# String_Thing_1_0.net
KiCad netlist of a schematic drawn in EAGLE
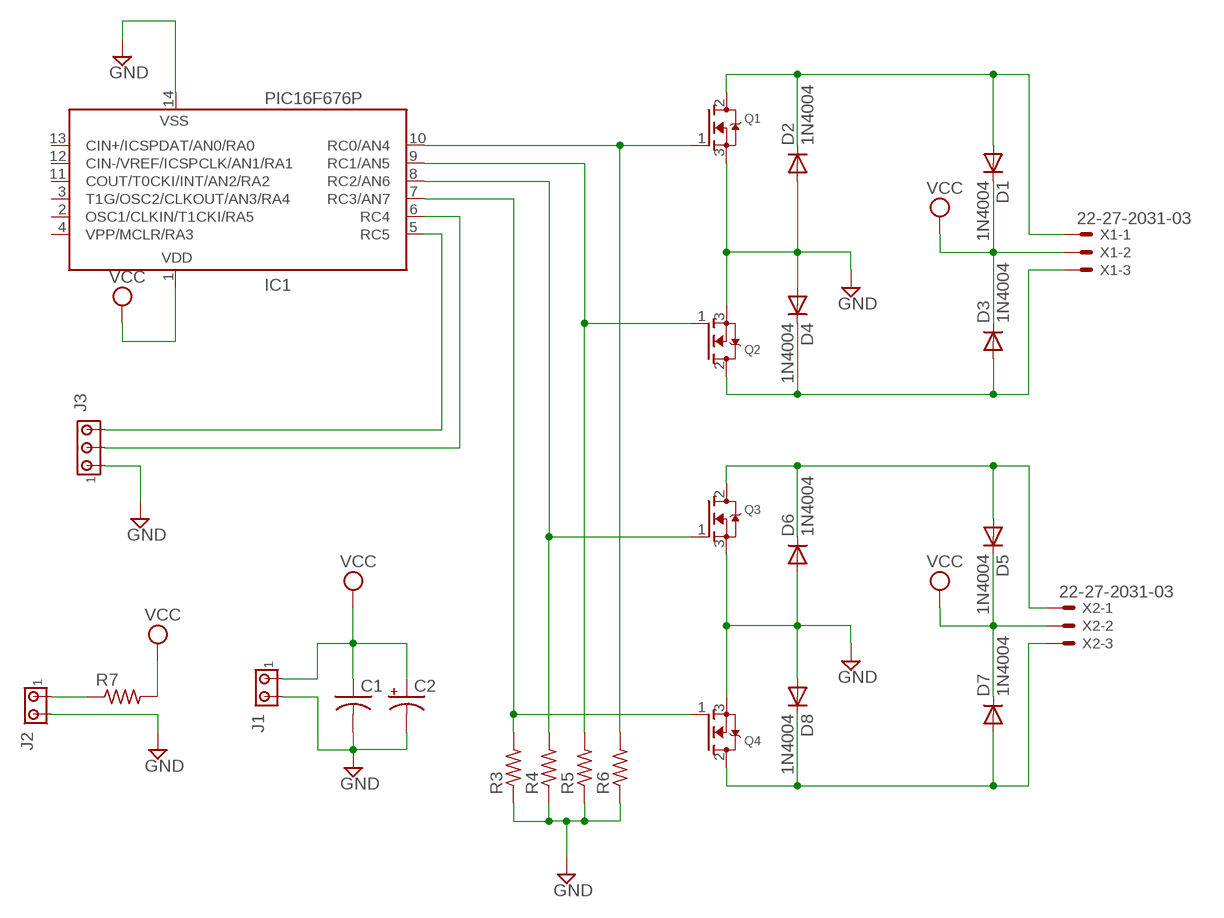
[diagram p0: schematic, sheet 1]

(export (version "E")
  (design (tool "Eeschema 10.0.6"))
  (components
    (comp (ref "C1")
      (value "C-US025-025X050")
      (footprint "eagle-import:C025-025X050")
      (libsource (lib "eagle-import") (part "C-US025-025X050"))
    )
    (comp (ref "C2")
      (value "CPOL-USE2.5-5")
      (footprint "eagle-import:E2,5-5")
      (libsource (lib "eagle-import") (part "CPOL-USE2.5-5"))
    )
    (comp (ref "D1")
      (value "1N4004")
      (footprint "eagle-import:DO41-10")
      (libsource (lib "eagle-import") (part "1N4004"))
    )
    (comp (ref "D2")
      (value "1N4004")
      (footprint "eagle-import:DO41-10")
      (libsource (lib "eagle-import") (part "1N4004"))
    )
    (comp (ref "D3")
      (value "1N4004")
      (footprint "eagle-import:DO41-10")
      (libsource (lib "eagle-import") (part "1N4004"))
    )
    (comp (ref "D4")
      (value "1N4004")
      (footprint "eagle-import:DO41-10")
      (libsource (lib "eagle-import") (part "1N4004"))
    )
    (comp (ref "D5")
      (value "1N4004")
      (footprint "eagle-import:DO41-10")
      (libsource (lib "eagle-import") (part "1N4004"))
    )
    (comp (ref "D6")
      (value "1N4004")
      (footprint "eagle-import:DO41-10")
      (libsource (lib "eagle-import") (part "1N4004"))
    )
    (comp (ref "D7")
      (value "1N4004")
      (footprint "eagle-import:DO41-10")
      (libsource (lib "eagle-import") (part "1N4004"))
    )
    (comp (ref "D8")
      (value "1N4004")
      (footprint "eagle-import:DO41-10")
      (libsource (lib "eagle-import") (part "1N4004"))
    )
    (comp (ref "IC1")
      (value "PIC16F676P")
      (footprint "eagle-import:DIL14")
      (fields (field (name "MF") "MICROCHIP") (field (name "MPN") "PIC16F676-I/P"))
      (libsource (lib "eagle-import") (part "PIC16F676P"))
    )
    (comp (ref "J1")
      (value "MTA02-100")
      (footprint "eagle-import:10X02MTA")
      (libsource (lib "eagle-import") (part "MTA02-100"))
    )
    (comp (ref "J2")
      (value "MTA02-100")
      (footprint "eagle-import:10X02MTA")
      (libsource (lib "eagle-import") (part "MTA02-100"))
    )
    (comp (ref "J3")
      (value "MTA03-100")
      (footprint "eagle-import:10X03MTA")
      (libsource (lib "eagle-import") (part "MTA03-100"))
    )
    (comp (ref "Q1")
      (value "MOSFET-NGDS_TO220V")
      (footprint "eagle-import:TO220V")
      (libsource (lib "eagle-import") (part "MOSFET-NGDS_TO220V"))
    )
    (comp (ref "Q2")
      (value "MOSFET-NGDS_TO220V")
      (footprint "eagle-import:TO220V")
      (libsource (lib "eagle-import") (part "MOSFET-NGDS_TO220V"))
    )
    (comp (ref "Q3")
      (value "MOSFET-NGDS_TO220V")
      (footprint "eagle-import:TO220V")
      (libsource (lib "eagle-import") (part "MOSFET-NGDS_TO220V"))
    )
    (comp (ref "Q4")
      (value "MOSFET-NGDS_TO220V")
      (footprint "eagle-import:TO220V")
      (libsource (lib "eagle-import") (part "MOSFET-NGDS_TO220V"))
    )
    (comp (ref "R3")
      (value "R-US_0207/10")
      (footprint "eagle-import:0207_10")
      (libsource (lib "eagle-import") (part "R-US_0207/10"))
    )
    (comp (ref "R4")
      (value "R-US_0207/10")
      (footprint "eagle-import:0207_10")
      (libsource (lib "eagle-import") (part "R-US_0207/10"))
    )
    (comp (ref "R5")
      (value "R-US_0207/10")
      (footprint "eagle-import:0207_10")
      (libsource (lib "eagle-import") (part "R-US_0207/10"))
    )
    (comp (ref "R6")
      (value "R-US_0207/10")
      (footprint "eagle-import:0207_10")
      (libsource (lib "eagle-import") (part "R-US_0207/10"))
    )
    (comp (ref "R7")
      (value "R-US_0207/10")
      (footprint "eagle-import:0207_10")
      (libsource (lib "eagle-import") (part "R-US_0207/10"))
    )
    (comp (ref "X1")
      (value "22-27-2031-03")
      (footprint "eagle-import:6410-03")
      (libsource (lib "eagle-import") (part "22-?-0327-2031"))
    )
    (comp (ref "X2")
      (value "22-27-2031-03")
      (footprint "eagle-import:6410-03")
      (libsource (lib "eagle-import") (part "22-?-0327-2031"))
    )
  )
  (nets
    (net (code "1") (name "GND") (class "Default")
      (node (ref "C1") (pin "2") (pinfunction "2_2") (pintype "passive"))
      (node (ref "C2") (pin "-") (pinfunction "-_-") (pintype "passive"))
      (node (ref "D2") (pin "A") (pinfunction "A_A") (pintype "passive"))
      (node (ref "D4") (pin "A") (pinfunction "A_A") (pintype "passive"))
      (node (ref "D6") (pin "A") (pinfunction "A_A") (pintype "passive"))
      (node (ref "D8") (pin "A") (pinfunction "A_A") (pintype "passive"))
      (node (ref "IC1") (pin "14") (pinfunction "VSS_14") (pintype "power_in"))
      (node (ref "J1") (pin "2") (pinfunction "2_2") (pintype "passive"))
      (node (ref "J2") (pin "2") (pinfunction "2_2") (pintype "passive"))
      (node (ref "J3") (pin "1") (pinfunction "1_1") (pintype "passive"))
      (node (ref "Q1") (pin "3") (pinfunction "S_3") (pintype "bidirectional"))
      (node (ref "Q2") (pin "3") (pinfunction "S_3") (pintype "bidirectional"))
      (node (ref "Q3") (pin "3") (pinfunction "S_3") (pintype "bidirectional"))
      (node (ref "Q4") (pin "3") (pinfunction "S_3") (pintype "bidirectional"))
      (node (ref "R3") (pin "1") (pinfunction "1_1") (pintype "passive"))
      (node (ref "R4") (pin "1") (pinfunction "1_1") (pintype "passive"))
      (node (ref "R5") (pin "1") (pinfunction "1_1") (pintype "passive"))
      (node (ref "R6") (pin "1") (pinfunction "1_1") (pintype "passive"))
    )
    (net (code "2") (name "Net-(IC1-RC0{slash}AN4)") (class "Default")
      (node (ref "IC1") (pin "10") (pinfunction "RC0/AN4_10") (pintype "bidirectional"))
      (node (ref "Q1") (pin "1") (pinfunction "G_1") (pintype "bidirectional"))
      (node (ref "R6") (pin "2") (pinfunction "2_2") (pintype "passive"))
    )
    (net (code "3") (name "Net-(IC1-RC1{slash}AN5)") (class "Default")
      (node (ref "IC1") (pin "9") (pinfunction "RC1/AN5_9") (pintype "bidirectional"))
      (node (ref "Q2") (pin "1") (pinfunction "G_1") (pintype "bidirectional"))
      (node (ref "R5") (pin "2") (pinfunction "2_2") (pintype "passive"))
    )
    (net (code "4") (name "Net-(IC1-RC2{slash}AN6)") (class "Default")
      (node (ref "IC1") (pin "8") (pinfunction "RC2/AN6_8") (pintype "bidirectional"))
      (node (ref "Q3") (pin "1") (pinfunction "G_1") (pintype "bidirectional"))
      (node (ref "R4") (pin "2") (pinfunction "2_2") (pintype "passive"))
    )
    (net (code "5") (name "Net-(IC1-RC3{slash}AN7)") (class "Default")
      (node (ref "IC1") (pin "7") (pinfunction "RC3/AN7_7") (pintype "bidirectional"))
      (node (ref "Q4") (pin "1") (pinfunction "G_1") (pintype "bidirectional"))
      (node (ref "R3") (pin "2") (pinfunction "2_2") (pintype "passive"))
    )
    (net (code "6") (name "Net-(IC1-RC4)") (class "Default")
      (node (ref "IC1") (pin "6") (pinfunction "RC4_6") (pintype "bidirectional"))
      (node (ref "J3") (pin "2") (pinfunction "2_2") (pintype "passive"))
    )
    (net (code "7") (name "Net-(IC1-RC5)") (class "Default")
      (node (ref "IC1") (pin "5") (pinfunction "RC5_5") (pintype "bidirectional"))
      (node (ref "J3") (pin "3") (pinfunction "3_3") (pintype "passive"))
    )
    (net (code "8") (name "Net-(J2-Pad1)") (class "Default")
      (node (ref "J2") (pin "1") (pinfunction "1_1") (pintype "passive"))
      (node (ref "R7") (pin "1") (pinfunction "1_1") (pintype "passive"))
    )
    (net (code "9") (name "Net-(Q1-D)") (class "Default")
      (node (ref "D1") (pin "A") (pinfunction "A_A") (pintype "passive"))
      (node (ref "D2") (pin "C") (pinfunction "C_C") (pintype "passive"))
      (node (ref "Q1") (pin "2") (pinfunction "D_2") (pintype "bidirectional"))
      (node (ref "X1") (pin "1") (pinfunction "S_1") (pintype "passive"))
    )
    (net (code "10") (name "Net-(Q2-D)") (class "Default")
      (node (ref "D3") (pin "A") (pinfunction "A_A") (pintype "passive"))
      (node (ref "D4") (pin "C") (pinfunction "C_C") (pintype "passive"))
      (node (ref "Q2") (pin "2") (pinfunction "D_2") (pintype "bidirectional"))
      (node (ref "X1") (pin "3") (pinfunction "S_3") (pintype "passive"))
    )
    (net (code "11") (name "Net-(Q3-D)") (class "Default")
      (node (ref "D5") (pin "A") (pinfunction "A_A") (pintype "passive"))
      (node (ref "D6") (pin "C") (pinfunction "C_C") (pintype "passive"))
      (node (ref "Q3") (pin "2") (pinfunction "D_2") (pintype "bidirectional"))
      (node (ref "X2") (pin "1") (pinfunction "S_1") (pintype "passive"))
    )
    (net (code "12") (name "Net-(Q4-D)") (class "Default")
      (node (ref "D7") (pin "A") (pinfunction "A_A") (pintype "passive"))
      (node (ref "D8") (pin "C") (pinfunction "C_C") (pintype "passive"))
      (node (ref "Q4") (pin "2") (pinfunction "D_2") (pintype "bidirectional"))
      (node (ref "X2") (pin "3") (pinfunction "S_3") (pintype "passive"))
    )
    (net (code "13") (name "VCC") (class "Default")
      (node (ref "C1") (pin "1") (pinfunction "1_1") (pintype "passive"))
      (node (ref "C2") (pin "+") (pinfunction "+_+") (pintype "passive"))
      (node (ref "D1") (pin "C") (pinfunction "C_C") (pintype "passive"))
      (node (ref "D3") (pin "C") (pinfunction "C_C") (pintype "passive"))
      (node (ref "D5") (pin "C") (pinfunction "C_C") (pintype "passive"))
      (node (ref "D7") (pin "C") (pinfunction "C_C") (pintype "passive"))
      (node (ref "IC1") (pin "1") (pinfunction "VDD_1") (pintype "power_in"))
      (node (ref "J1") (pin "1") (pinfunction "1_1") (pintype "passive"))
      (node (ref "R7") (pin "2") (pinfunction "2_2") (pintype "passive"))
      (node (ref "X1") (pin "2") (pinfunction "S_2") (pintype "passive"))
      (node (ref "X2") (pin "2") (pinfunction "S_2") (pintype "passive"))
    )
    (net (code "14") (name "unconnected-(IC1-CIN+{slash}ICSPDAT{slash}AN0{slash}RA0-Pad13)") (class "Default")
      (node (ref "IC1") (pin "13") (pinfunction "CIN+/ICSPDAT/AN0/RA0_13") (pintype "bidirectional"))
    )
    (net (code "15") (name "unconnected-(IC1-CIN-{slash}VREF{slash}ICSPCLK{slash}AN1{slash}RA1-Pad12)") (class "Default")
      (node (ref "IC1") (pin "12") (pinfunction "CIN-/VREF/ICSPCLK/AN1/RA1_12") (pintype "bidirectional"))
    )
    (net (code "16") (name "unconnected-(IC1-COUT{slash}T0CKI{slash}INT{slash}AN2{slash}RA2-Pad11)") (class "Default")
      (node (ref "IC1") (pin "11") (pinfunction "COUT/T0CKI/INT/AN2/RA2_11") (pintype "bidirectional"))
    )
    (net (code "17") (name "unconnected-(IC1-OSC1{slash}CLKIN{slash}T1CKI{slash}RA5-Pad2)") (class "Default")
      (node (ref "IC1") (pin "2") (pinfunction "OSC1/CLKIN/T1CKI/RA5_2") (pintype "bidirectional"))
    )
    (net (code "18") (name "unconnected-(IC1-T1G{slash}OSC2{slash}CLKOUT{slash}AN3{slash}RA4-Pad3)") (class "Default")
      (node (ref "IC1") (pin "3") (pinfunction "T1G/OSC2/CLKOUT/AN3/RA4_3") (pintype "bidirectional"))
    )
    (net (code "19") (name "unconnected-(IC1-VPP{slash}MCLR{slash}RA3-Pad4)") (class "Default")
      (node (ref "IC1") (pin "4") (pinfunction "VPP/MCLR/RA3_4") (pintype "input"))
    )
  )
)
